# Alimentaci_n.net
KiCad netlist of a schematic drawn in Altium Designer
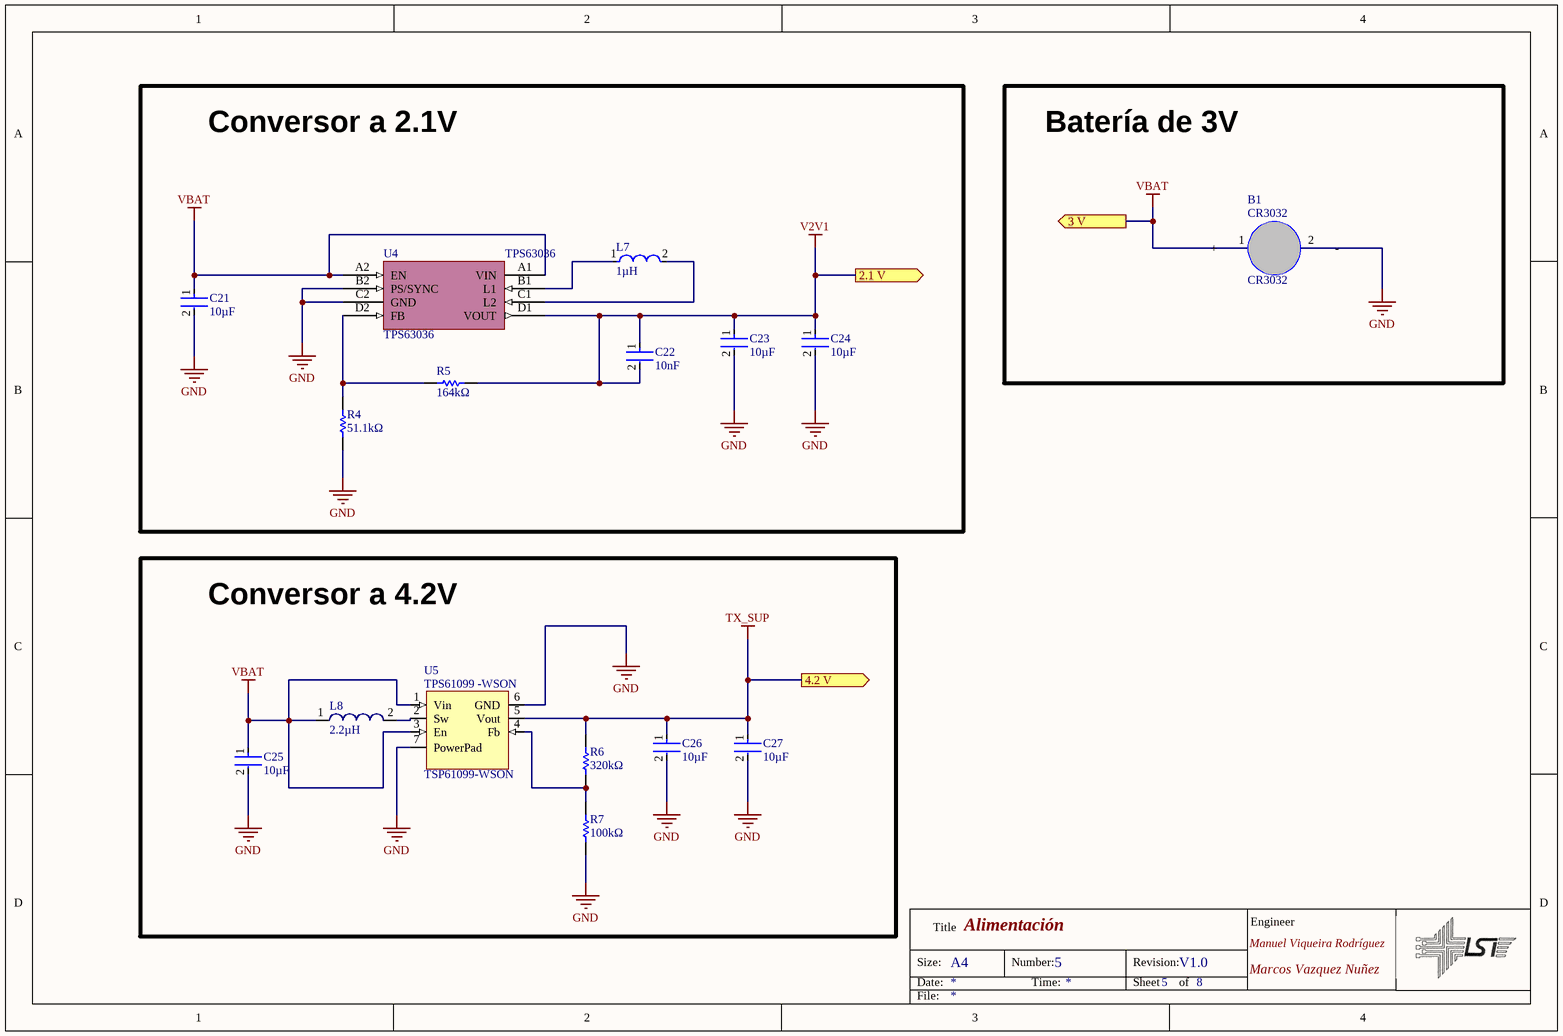
[diagram p0: Alimentación.SchDoc]

(export (version "E")
  (design (tool "Eeschema 10.0.6"))
  (components
    (comp (ref "B1") (value "CR3032") (footprint "CR3032") (libsource (lib "DEOP2021") (part "CR3032")))
    (comp (ref "C21")
      (value "10µF")
      (footprint "FP-CL10-IPC_B")
      (description "Cap Ceramic 10uF 10V X5R ±10% Pad SMD 0603 +85°C T/R")
      (fields (field (name "TOLERANCE") "10%"))
      (libsource (lib "Altium Content Vault") (part "b4654b650e69147ec39a6b967a45e02"))
    )
    (comp (ref "C22")
      (value "10nF")
      (footprint "FP-CL10-IPC_C")
      (description "Cap Ceramic 10nF 50V X7R ±20% Pad SMD 0603 +125°C T/R")
      (fields (field (name "TOLERANCE") "20%"))
      (libsource (lib "Altium Content Vault") (part "b4654b650e69147ec39a6b967a45e02"))
    )
    (comp (ref "C23")
      (value "10µF")
      (footprint "FP-CL10-IPC_B")
      (description "Cap Ceramic 10uF 10V X5R ±10% Pad SMD 0603 +85°C T/R")
      (fields (field (name "TOLERANCE") "10%"))
      (libsource (lib "Altium Content Vault") (part "b4654b650e69147ec39a6b967a45e02"))
    )
    (comp (ref "C24")
      (value "10µF")
      (footprint "FP-CL10-IPC_B")
      (description "Cap Ceramic 10uF 10V X5R ±10% Pad SMD 0603 +85°C T/R")
      (fields (field (name "TOLERANCE") "10%"))
      (libsource (lib "Altium Content Vault") (part "b4654b650e69147ec39a6b967a45e02"))
    )
    (comp (ref "C25")
      (value "10µF")
      (footprint "FP-CL10-IPC_B")
      (description "Cap Ceramic 10uF 10V X5R ±10% Pad SMD 0603 +85°C T/R")
      (fields (field (name "TOLERANCE") "10%"))
      (libsource (lib "Altium Content Vault") (part "b4654b650e69147ec39a6b967a45e02"))
    )
    (comp (ref "C26")
      (value "10µF")
      (footprint "FP-CL10-IPC_B")
      (description "Cap Ceramic 10uF 10V X5R ±10% Pad SMD 0603 +85°C T/R")
      (fields (field (name "TOLERANCE") "10%"))
      (libsource (lib "Altium Content Vault") (part "b4654b650e69147ec39a6b967a45e02"))
    )
    (comp (ref "C27")
      (value "10µF")
      (footprint "FP-CL10-IPC_B")
      (description "Cap Ceramic 10uF 10V X5R ±10% Pad SMD 0603 +85°C T/R")
      (fields (field (name "TOLERANCE") "10%"))
      (libsource (lib "Altium Content Vault") (part "b4654b650e69147ec39a6b967a45e02"))
    )
    (comp (ref "L7")
      (value "1µH")
      (footprint "FP-MLZ1608-MFG")
      (description "FIXED IND 1UH 600MA 150 MOHM SMD")
      (fields (field (name "MANUFACTURER PART NUMBER") "MLZ1608A1R0WT000") (field (name "TOLERANCE") "20%"))
      (libsource (lib "Altium Content Vault") (part "725321dda6339637d4d059423bc1c3c"))
    )
    (comp (ref "L8")
      (value "2.2µH")
      (footprint "SMD 2508")
      (description "Power Multilayer Inductor WE-MAPI, L=2.2µH")
      (fields (field (name "PARTNUMBER") "74438322022") (field (name "MANUFACTURER") "Wuerth Elektronik"))
      (libsource (lib "Altium Content Vault") (part "WE-IND-INDUCTOR-2"))
    )
    (comp (ref "R4")
      (value "51.1kΩ")
      (footprint "RESC1005X40X25NL05T10")
      (fields (field (name "PART NUMBER") "ERJ-U02F1501X") (field (name "MANUFACTURER") "Panasonic"))
      (libsource (lib "Altium Content Vault") (part "RES"))
    )
    (comp (ref "R5")
      (value "164kΩ")
      (footprint "RESC1005X40X25NL05T10")
      (fields (field (name "PART NUMBER") "ERJ-U02F1501X") (field (name "MANUFACTURER") "Panasonic"))
      (libsource (lib "Altium Content Vault") (part "RES"))
    )
    (comp (ref "R6")
      (value "320kΩ")
      (footprint "RESC1005X40X25NL05T10")
      (fields (field (name "PART NUMBER") "ERJ-U02F1501X") (field (name "MANUFACTURER") "Panasonic"))
      (libsource (lib "Altium Content Vault") (part "RES"))
    )
    (comp (ref "R7")
      (value "100kΩ")
      (footprint "RESC1005X40X25NL05T10")
      (fields (field (name "PART NUMBER") "ERJ-U02F1501X") (field (name "MANUFACTURER") "Panasonic"))
      (libsource (lib "Altium Content Vault") (part "RES"))
    )
    (comp (ref "U4") (value "TPS63036") (footprint "tps63036") (libsource (lib "DEOP2021") (part "TPS63036")))
    (comp (ref "U5")
      (value "TSP61099-WSON")
      (footprint "SOP6")
      (libsource (lib "DEOP2021") (part "TSP61099-WSON"))
    )
  )
  (nets
    (net (code "1") (name "GND") (class "Default")
      (node (ref "B1") (pin "2") (pinfunction "-_2") (pintype "passive"))
      (node (ref "C21") (pin "2") (pinfunction "2_2") (pintype "passive"))
      (node (ref "C23") (pin "2") (pinfunction "2_2") (pintype "passive"))
      (node (ref "C24") (pin "2") (pinfunction "2_2") (pintype "passive"))
      (node (ref "C25") (pin "2") (pinfunction "2_2") (pintype "passive"))
      (node (ref "C26") (pin "2") (pinfunction "2_2") (pintype "passive"))
      (node (ref "C27") (pin "2") (pinfunction "2_2") (pintype "passive"))
      (node (ref "R4") (pin "1") (pinfunction "1_1") (pintype "passive"))
      (node (ref "R7") (pin "1") (pinfunction "1_1") (pintype "passive"))
      (node (ref "U4") (pin "B2") (pinfunction "PS/SYNC_B2") (pintype "input"))
      (node (ref "U4") (pin "C2") (pinfunction "GND_C2") (pintype "power_in"))
      (node (ref "U5") (pin "6") (pinfunction "GND_6") (pintype "power_in"))
      (node (ref "U5") (pin "7") (pinfunction "PowerPad_7") (pintype "power_in"))
    )
    (net (code "2") (name "Net-(U4-FB)") (class "Default")
      (node (ref "R4") (pin "2") (pinfunction "2_2") (pintype "passive"))
      (node (ref "R5") (pin "1") (pinfunction "1_1") (pintype "passive"))
      (node (ref "U4") (pin "D2") (pinfunction "FB_D2") (pintype "input"))
    )
    (net (code "3") (name "Net-(U4-L1)") (class "Default")
      (node (ref "L7") (pin "1") (pinfunction "1_1") (pintype "passive"))
      (node (ref "U4") (pin "B1") (pinfunction "L1_B1") (pintype "input"))
    )
    (net (code "4") (name "Net-(U4-L2)") (class "Default")
      (node (ref "L7") (pin "2") (pinfunction "2_2") (pintype "passive"))
      (node (ref "U4") (pin "C1") (pinfunction "L2_C1") (pintype "input"))
    )
    (net (code "5") (name "Net-(U5-Fb)") (class "Default")
      (node (ref "R6") (pin "1") (pinfunction "1_1") (pintype "passive"))
      (node (ref "R7") (pin "2") (pinfunction "2_2") (pintype "passive"))
      (node (ref "U5") (pin "4") (pinfunction "Fb_4") (pintype "input"))
    )
    (net (code "6") (name "Net-(U5-Sw)") (class "Default")
      (node (ref "L8") (pin "2") (pinfunction "2_2") (pintype "passive"))
      (node (ref "U5") (pin "2") (pinfunction "Sw_2") (pintype "power_in"))
    )
    (net (code "7") (name "TX_SUP") (class "Default")
      (node (ref "C26") (pin "1") (pinfunction "1_1") (pintype "passive"))
      (node (ref "C27") (pin "1") (pinfunction "1_1") (pintype "passive"))
      (node (ref "R6") (pin "2") (pinfunction "2_2") (pintype "passive"))
      (node (ref "U5") (pin "5") (pinfunction "Vout_5") (pintype "power_in"))
    )
    (net (code "8") (name "V2V1") (class "Default")
      (node (ref "C22") (pin "1") (pinfunction "1_1") (pintype "passive"))
      (node (ref "C22") (pin "2") (pinfunction "2_2") (pintype "passive"))
      (node (ref "C23") (pin "1") (pinfunction "1_1") (pintype "passive"))
      (node (ref "C24") (pin "1") (pinfunction "1_1") (pintype "passive"))
      (node (ref "R5") (pin "2") (pinfunction "2_2") (pintype "passive"))
      (node (ref "U4") (pin "D1") (pinfunction "VOUT_D1") (pintype "output"))
    )
    (net (code "9") (name "VBAT") (class "Default")
      (node (ref "B1") (pin "1") (pinfunction "+_1") (pintype "passive"))
      (node (ref "C21") (pin "1") (pinfunction "1_1") (pintype "passive"))
      (node (ref "C25") (pin "1") (pinfunction "1_1") (pintype "passive"))
      (node (ref "L8") (pin "1") (pinfunction "1_1") (pintype "passive"))
      (node (ref "U4") (pin "A1") (pinfunction "VIN_A1") (pintype "power_in"))
      (node (ref "U4") (pin "A2") (pinfunction "EN_A2") (pintype "input"))
      (node (ref "U5") (pin "1") (pinfunction "Vin_1") (pintype "input"))
      (node (ref "U5") (pin "3") (pinfunction "En_3") (pintype "input"))
    )
  )
)
